# cpu_board.net
KiCad netlist of a schematic drawn in EAGLE
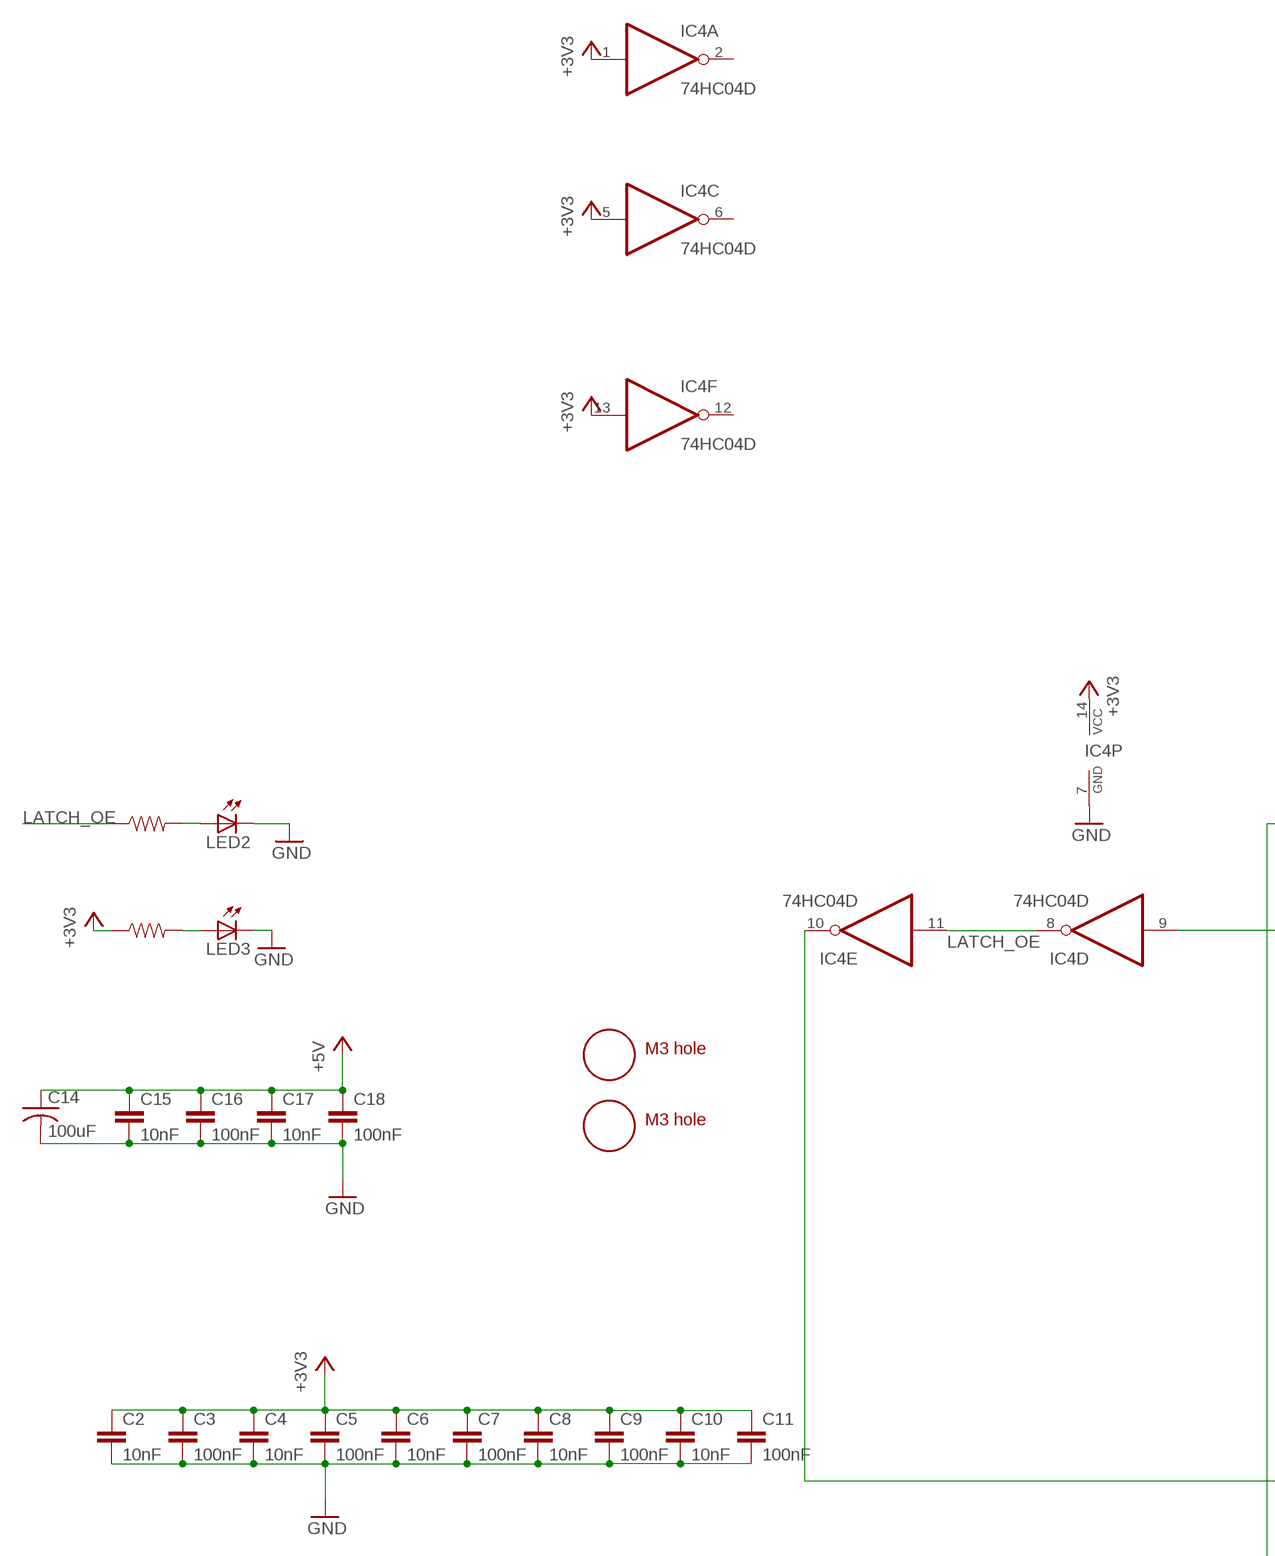
[diagram p0: schematic, sheet 1, part 1 of 2]
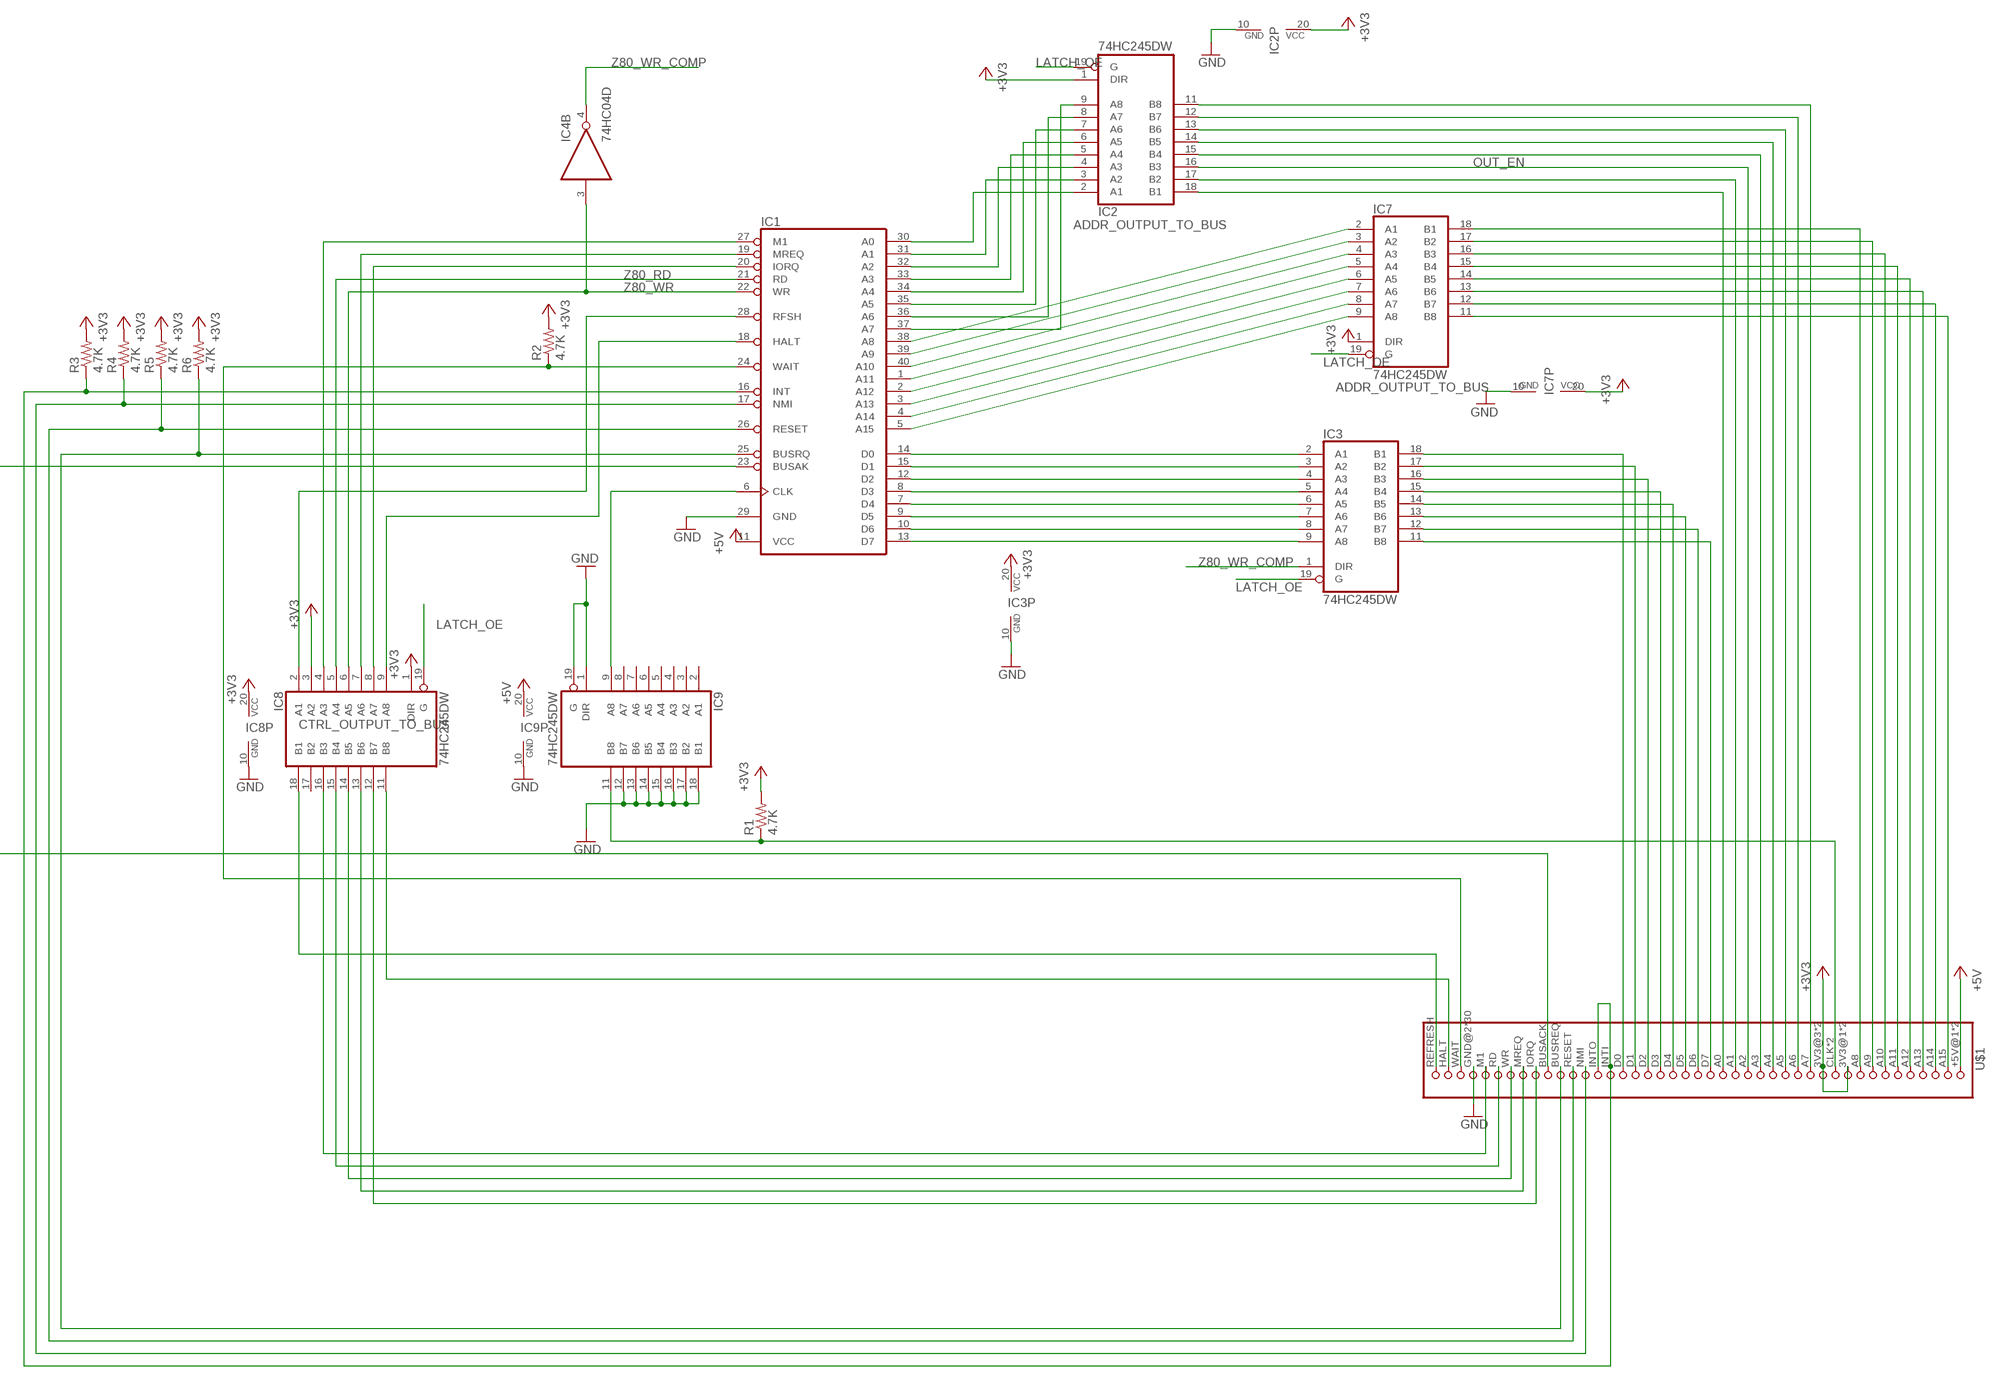
[diagram p1: schematic, sheet 1, part 2 of 2]

(export (version "E")
  (design (tool "Eeschema 10.0.6"))
  (components
    (comp (ref "C2")
      (value "10nF")
      (footprint "eagle-import:0805")
      (libsource (lib "eagle-import") (part "22UF-6.3V-20%(0805)"))
    )
    (comp (ref "C3")
      (value "100nF")
      (footprint "eagle-import:0805")
      (libsource (lib "eagle-import") (part "22UF-6.3V-20%(0805)"))
    )
    (comp (ref "C4")
      (value "10nF")
      (footprint "eagle-import:0805")
      (libsource (lib "eagle-import") (part "22UF-6.3V-20%(0805)"))
    )
    (comp (ref "C5")
      (value "100nF")
      (footprint "eagle-import:0805")
      (libsource (lib "eagle-import") (part "22UF-6.3V-20%(0805)"))
    )
    (comp (ref "C6")
      (value "10nF")
      (footprint "eagle-import:0805")
      (libsource (lib "eagle-import") (part "22UF-6.3V-20%(0805)"))
    )
    (comp (ref "C7")
      (value "100nF")
      (footprint "eagle-import:0805")
      (libsource (lib "eagle-import") (part "22UF-6.3V-20%(0805)"))
    )
    (comp (ref "C8")
      (value "10nF")
      (footprint "eagle-import:0805")
      (libsource (lib "eagle-import") (part "22UF-6.3V-20%(0805)"))
    )
    (comp (ref "C9")
      (value "100nF")
      (footprint "eagle-import:0805")
      (libsource (lib "eagle-import") (part "22UF-6.3V-20%(0805)"))
    )
    (comp (ref "C10")
      (value "10nF")
      (footprint "eagle-import:0805")
      (libsource (lib "eagle-import") (part "22UF-6.3V-20%(0805)"))
    )
    (comp (ref "C11")
      (value "100nF")
      (footprint "eagle-import:0805")
      (libsource (lib "eagle-import") (part "22UF-6.3V-20%(0805)"))
    )
    (comp (ref "C14")
      (value "100uF")
      (footprint "eagle-import:C1210")
      (libsource (lib "eagle-import") (part "C-USC1210"))
    )
    (comp (ref "C15")
      (value "10nF")
      (footprint "eagle-import:0805")
      (libsource (lib "eagle-import") (part "22UF-6.3V-20%(0805)"))
    )
    (comp (ref "C16")
      (value "100nF")
      (footprint "eagle-import:0805")
      (libsource (lib "eagle-import") (part "22UF-6.3V-20%(0805)"))
    )
    (comp (ref "C17")
      (value "10nF")
      (footprint "eagle-import:0805")
      (libsource (lib "eagle-import") (part "22UF-6.3V-20%(0805)"))
    )
    (comp (ref "C18")
      (value "100nF")
      (footprint "eagle-import:0805")
      (libsource (lib "eagle-import") (part "22UF-6.3V-20%(0805)"))
    )
    (comp (ref "IC1")
      (value "Z80CPU")
      (footprint "eagle-import:DIL40")
      (libsource (lib "eagle-import") (part "Z80CPU"))
    )
    (comp (ref "IC2")
      (value "74HC245DW")
      (footprint "eagle-import:SO20W")
      (libsource (lib "eagle-import") (part "74245DWHC"))
    )
    (comp (ref "IC3")
      (value "74HC245DW")
      (footprint "eagle-import:SO20W")
      (libsource (lib "eagle-import") (part "74245DWHC"))
    )
    (comp (ref "IC4")
      (value "74HC04D")
      (footprint "eagle-import:SO14")
      (libsource (lib "eagle-import") (part "7404DHC"))
    )
    (comp (ref "IC7")
      (value "74HC245DW")
      (footprint "eagle-import:SO20W")
      (libsource (lib "eagle-import") (part "74245DWHC"))
    )
    (comp (ref "IC8")
      (value "74HC245DW")
      (footprint "eagle-import:SO20W")
      (libsource (lib "eagle-import") (part "74245DWHC"))
    )
    (comp (ref "IC9")
      (value "74HC245DW")
      (footprint "eagle-import:SO20W")
      (libsource (lib "eagle-import") (part "74245DWHC"))
    )
    (comp (ref "LED2")
      (value "LEDCHIP-LED0805")
      (footprint "eagle-import:CHIP-LED0805")
      (libsource (lib "eagle-import") (part "LEDCHIP-LED0805"))
    )
    (comp (ref "LED3")
      (value "LEDCHIP-LED0805")
      (footprint "eagle-import:CHIP-LED0805")
      (libsource (lib "eagle-import") (part "LEDCHIP-LED0805"))
    )
    (comp (ref "R1")
      (value "4.7K")
      (footprint "eagle-import:0805")
      (libsource (lib "eagle-import") (part "SparkFun-Resistors_RESISTOR0805-RES"))
    )
    (comp (ref "R2")
      (value "4.7K")
      (footprint "eagle-import:0805")
      (libsource (lib "eagle-import") (part "SparkFun-Resistors_RESISTOR0805-RES"))
    )
    (comp (ref "R3")
      (value "4.7K")
      (footprint "eagle-import:0805")
      (libsource (lib "eagle-import") (part "SparkFun-Resistors_RESISTOR0805-RES"))
    )
    (comp (ref "R4")
      (value "4.7K")
      (footprint "eagle-import:0805")
      (libsource (lib "eagle-import") (part "SparkFun-Resistors_RESISTOR0805-RES"))
    )
    (comp (ref "R5")
      (value "4.7K")
      (footprint "eagle-import:0805")
      (libsource (lib "eagle-import") (part "SparkFun-Resistors_RESISTOR0805-RES"))
    )
    (comp (ref "R6")
      (value "4.7K")
      (footprint "eagle-import:0805")
      (libsource (lib "eagle-import") (part "SparkFun-Resistors_RESISTOR0805-RES"))
    )
    (comp (ref "R7")
      (value "2K")
      (footprint "eagle-import:0805")
      (libsource (lib "eagle-import") (part "RESISTOR0805-RES"))
    )
    (comp (ref "R8")
      (value "2K")
      (footprint "eagle-import:0805")
      (libsource (lib "eagle-import") (part "RESISTOR0805-RES"))
    )
    (comp (ref "U$1")
      (value "FAP_BUS")
      (footprint "eagle-import:2X38")
      (libsource (lib "eagle-import") (part "FAP_BUS"))
    )
    (comp (ref "U$2")
      (value "M3_MOUNTING_HOLE")
      (footprint "eagle-import:M3_MOUNTING_HOLE_PACK")
      (libsource (lib "eagle-import") (part "M3_MOUNTING_HOLE"))
    )
    (comp (ref "U$3")
      (value "M3_MOUNTING_HOLE")
      (footprint "eagle-import:M3_MOUNTING_HOLE_PACK")
      (libsource (lib "eagle-import") (part "M3_MOUNTING_HOLE"))
    )
  )
  (nets
    (net (code "1") (name "+3V3") (class "Default")
      (node (ref "C10") (pin "1") (pinfunction "1_1") (pintype "passive"))
      (node (ref "C11") (pin "1") (pinfunction "1_1") (pintype "passive"))
      (node (ref "C2") (pin "1") (pinfunction "1_1") (pintype "passive"))
      (node (ref "C3") (pin "1") (pinfunction "1_1") (pintype "passive"))
      (node (ref "C4") (pin "1") (pinfunction "1_1") (pintype "passive"))
      (node (ref "C5") (pin "1") (pinfunction "1_1") (pintype "passive"))
      (node (ref "C6") (pin "1") (pinfunction "1_1") (pintype "passive"))
      (node (ref "C7") (pin "1") (pinfunction "1_1") (pintype "passive"))
      (node (ref "C8") (pin "1") (pinfunction "1_1") (pintype "passive"))
      (node (ref "C9") (pin "1") (pinfunction "1_1") (pintype "passive"))
      (node (ref "IC2") (pin "1") (pinfunction "DIR_1") (pintype "input"))
      (node (ref "IC2") (pin "20") (pinfunction "VCC_20") (pintype "power_in"))
      (node (ref "IC3") (pin "20") (pinfunction "VCC_20") (pintype "power_in"))
      (node (ref "IC4") (pin "1") (pinfunction "I_1") (pintype "input"))
      (node (ref "IC4") (pin "13") (pinfunction "I_13") (pintype "input"))
      (node (ref "IC4") (pin "14") (pinfunction "VCC_14") (pintype "power_in"))
      (node (ref "IC4") (pin "5") (pinfunction "I_5") (pintype "input"))
      (node (ref "IC7") (pin "1") (pinfunction "DIR_1") (pintype "input"))
      (node (ref "IC7") (pin "20") (pinfunction "VCC_20") (pintype "power_in"))
      (node (ref "IC8") (pin "1") (pinfunction "DIR_1") (pintype "input"))
      (node (ref "IC8") (pin "20") (pinfunction "VCC_20") (pintype "power_in"))
      (node (ref "IC8") (pin "3") (pinfunction "A2_3") (pintype "bidirectional"))
      (node (ref "R1") (pin "2") (pinfunction "2_2") (pintype "passive"))
      (node (ref "R2") (pin "2") (pinfunction "2_2") (pintype "passive"))
      (node (ref "R3") (pin "2") (pinfunction "2_2") (pintype "passive"))
      (node (ref "R4") (pin "2") (pinfunction "2_2") (pintype "passive"))
      (node (ref "R5") (pin "2") (pinfunction "2_2") (pintype "passive"))
      (node (ref "R6") (pin "2") (pinfunction "2_2") (pintype "passive"))
      (node (ref "R8") (pin "1") (pinfunction "1_1") (pintype "passive"))
      (node (ref "U$1") (pin "3V3@1") (pinfunction "10_3V3@1") (pintype "passive"))
      (node (ref "U$1") (pin "3V3@2") (pinfunction "10_3V3@2") (pintype "passive"))
      (node (ref "U$1") (pin "3V3@3") (pinfunction "12_3V3@3") (pintype "passive"))
      (node (ref "U$1") (pin "3V3@4") (pinfunction "12_3V3@4") (pintype "passive"))
    )
    (net (code "2") (name "+5V") (class "Default")
      (node (ref "C14") (pin "1") (pinfunction "1_1") (pintype "passive"))
      (node (ref "C15") (pin "1") (pinfunction "1_1") (pintype "passive"))
      (node (ref "C16") (pin "1") (pinfunction "1_1") (pintype "passive"))
      (node (ref "C17") (pin "1") (pinfunction "1_1") (pintype "passive"))
      (node (ref "C18") (pin "1") (pinfunction "1_1") (pintype "passive"))
      (node (ref "IC1") (pin "11") (pinfunction "VCC_11") (pintype "power_in"))
      (node (ref "IC9") (pin "20") (pinfunction "VCC_20") (pintype "power_in"))
      (node (ref "U$1") (pin "+5V@1") (pinfunction "1_+5V@1") (pintype "passive"))
      (node (ref "U$1") (pin "+5V@2") (pinfunction "1_+5V@2") (pintype "passive"))
    )
    (net (code "3") (name "/LATCH_OE") (class "Default")
      (node (ref "IC2") (pin "19") (pinfunction "G_19") (pintype "input"))
      (node (ref "IC3") (pin "19") (pinfunction "G_19") (pintype "input"))
      (node (ref "IC4") (pin "11") (pinfunction "I_11") (pintype "input"))
      (node (ref "IC4") (pin "8") (pinfunction "O_8") (pintype "output"))
      (node (ref "IC7") (pin "19") (pinfunction "G_19") (pintype "input"))
      (node (ref "IC8") (pin "19") (pinfunction "G_19") (pintype "input"))
      (node (ref "R7") (pin "1") (pinfunction "1_1") (pintype "passive"))
    )
    (net (code "4") (name "/OUT_EN") (class "Default")
      (node (ref "IC2") (pin "16") (pinfunction "B3_16") (pintype "bidirectional"))
      (node (ref "U$1") (pin "A2") (pinfunction "18_A2") (pintype "passive"))
    )
    (net (code "5") (name "/Z80_RD") (class "Default")
      (node (ref "IC1") (pin "21") (pinfunction "RD_21") (pintype "output"))
      (node (ref "IC8") (pin "5") (pinfunction "A4_5") (pintype "bidirectional"))
    )
    (net (code "6") (name "/Z80_WR") (class "Default")
      (node (ref "IC1") (pin "22") (pinfunction "WR_22") (pintype "output"))
      (node (ref "IC4") (pin "3") (pinfunction "I_3") (pintype "input"))
      (node (ref "IC8") (pin "6") (pinfunction "A5_6") (pintype "bidirectional"))
    )
    (net (code "7") (name "/Z80_WR_COMP") (class "Default")
      (node (ref "IC3") (pin "1") (pinfunction "DIR_1") (pintype "input"))
      (node (ref "IC4") (pin "4") (pinfunction "O_4") (pintype "output"))
    )
    (net (code "8") (name "GND") (class "Default")
      (node (ref "C10") (pin "2") (pinfunction "2_2") (pintype "passive"))
      (node (ref "C11") (pin "2") (pinfunction "2_2") (pintype "passive"))
      (node (ref "C14") (pin "2") (pinfunction "2_2") (pintype "passive"))
      (node (ref "C15") (pin "2") (pinfunction "2_2") (pintype "passive"))
      (node (ref "C16") (pin "2") (pinfunction "2_2") (pintype "passive"))
      (node (ref "C17") (pin "2") (pinfunction "2_2") (pintype "passive"))
      (node (ref "C18") (pin "2") (pinfunction "2_2") (pintype "passive"))
      (node (ref "C2") (pin "2") (pinfunction "2_2") (pintype "passive"))
      (node (ref "C3") (pin "2") (pinfunction "2_2") (pintype "passive"))
      (node (ref "C4") (pin "2") (pinfunction "2_2") (pintype "passive"))
      (node (ref "C5") (pin "2") (pinfunction "2_2") (pintype "passive"))
      (node (ref "C6") (pin "2") (pinfunction "2_2") (pintype "passive"))
      (node (ref "C7") (pin "2") (pinfunction "2_2") (pintype "passive"))
      (node (ref "C8") (pin "2") (pinfunction "2_2") (pintype "passive"))
      (node (ref "C9") (pin "2") (pinfunction "2_2") (pintype "passive"))
      (node (ref "IC1") (pin "29") (pinfunction "GND_29") (pintype "power_in"))
      (node (ref "IC2") (pin "10") (pinfunction "GND_10") (pintype "power_in"))
      (node (ref "IC3") (pin "10") (pinfunction "GND_10") (pintype "power_in"))
      (node (ref "IC4") (pin "7") (pinfunction "GND_7") (pintype "power_in"))
      (node (ref "IC7") (pin "10") (pinfunction "GND_10") (pintype "power_in"))
      (node (ref "IC8") (pin "10") (pinfunction "GND_10") (pintype "power_in"))
      (node (ref "IC9") (pin "1") (pinfunction "DIR_1") (pintype "input"))
      (node (ref "IC9") (pin "10") (pinfunction "GND_10") (pintype "power_in"))
      (node (ref "IC9") (pin "12") (pinfunction "B7_12") (pintype "bidirectional"))
      (node (ref "IC9") (pin "13") (pinfunction "B6_13") (pintype "bidirectional"))
      (node (ref "IC9") (pin "14") (pinfunction "B5_14") (pintype "bidirectional"))
      (node (ref "IC9") (pin "15") (pinfunction "B4_15") (pintype "bidirectional"))
      (node (ref "IC9") (pin "16") (pinfunction "B3_16") (pintype "bidirectional"))
      (node (ref "IC9") (pin "17") (pinfunction "B2_17") (pintype "bidirectional"))
      (node (ref "IC9") (pin "18") (pinfunction "B1_18") (pintype "bidirectional"))
      (node (ref "IC9") (pin "19") (pinfunction "G_19") (pintype "input"))
      (node (ref "LED2") (pin "C") (pinfunction "C_C") (pintype "passive"))
      (node (ref "LED3") (pin "C") (pinfunction "C_C") (pintype "passive"))
      (node (ref "U$1") (pin "GND@13") (pinfunction "GND_GND@13") (pintype "passive"))
      (node (ref "U$1") (pin "GND@14") (pinfunction "GND_GND@14") (pintype "passive"))
      (node (ref "U$1") (pin "GND@15") (pinfunction "GND_GND@15") (pintype "passive"))
      (node (ref "U$1") (pin "GND@16") (pinfunction "GND_GND@16") (pintype "passive"))
      (node (ref "U$1") (pin "GND@17") (pinfunction "GND_GND@17") (pintype "passive"))
      (node (ref "U$1") (pin "GND@18") (pinfunction "GND_GND@18") (pintype "passive"))
      (node (ref "U$1") (pin "GND@19") (pinfunction "GND_GND@19") (pintype "passive"))
      (node (ref "U$1") (pin "GND@2") (pinfunction "GND_GND@2") (pintype "passive"))
      (node (ref "U$1") (pin "GND@20") (pinfunction "GND_GND@20") (pintype "passive"))
      (node (ref "U$1") (pin "GND@21") (pinfunction "GND_GND@21") (pintype "passive"))
      (node (ref "U$1") (pin "GND@22") (pinfunction "GND_GND@22") (pintype "passive"))
      (node (ref "U$1") (pin "GND@23") (pinfunction "GND_GND@23") (pintype "passive"))
      (node (ref "U$1") (pin "GND@24") (pinfunction "GND_GND@24") (pintype "passive"))
      (node (ref "U$1") (pin "GND@25") (pinfunction "GND_GND@25") (pintype "passive"))
      (node (ref "U$1") (pin "GND@26") (pinfunction "GND_GND@26") (pintype "passive"))
      (node (ref "U$1") (pin "GND@27") (pinfunction "GND_GND@27") (pintype "passive"))
      (node (ref "U$1") (pin "GND@28") (pinfunction "GND_GND@28") (pintype "passive"))
      (node (ref "U$1") (pin "GND@3") (pinfunction "GND_GND@3") (pintype "passive"))
      (node (ref "U$1") (pin "GND@30") (pinfunction "GND_GND@30") (pintype "passive"))
      (node (ref "U$1") (pin "GND@34") (pinfunction "GND_GND@34") (pintype "passive"))
      (node (ref "U$1") (pin "GND@35") (pinfunction "GND_GND@35") (pintype "passive"))
      (node (ref "U$1") (pin "GND@36") (pinfunction "GND_GND@36") (pintype "passive"))
      (node (ref "U$1") (pin "GND@37") (pinfunction "GND_GND@37") (pintype "passive"))
      (node (ref "U$1") (pin "GND@38") (pinfunction "GND_GND@38") (pintype "passive"))
      (node (ref "U$1") (pin "GND@4") (pinfunction "GND_GND@4") (pintype "passive"))
      (node (ref "U$1") (pin "GND@5") (pinfunction "GND_GND@5") (pintype "passive"))
      (node (ref "U$1") (pin "GND@6") (pinfunction "GND_GND@6") (pintype "passive"))
      (node (ref "U$1") (pin "GND@7") (pinfunction "GND_GND@7") (pintype "passive"))
      (node (ref "U$1") (pin "GND@8") (pinfunction "GND_GND@8") (pintype "passive"))
      (node (ref "U$1") (pin "GND@9") (pinfunction "GND_GND@9") (pintype "passive"))
    )
    (net (code "9") (name "Net-(IC1-A0)") (class "Default")
      (node (ref "IC1") (pin "30") (pinfunction "A0_30") (pintype "output"))
      (node (ref "IC2") (pin "2") (pinfunction "A1_2") (pintype "bidirectional"))
    )
    (net (code "10") (name "Net-(IC1-A1)") (class "Default")
      (node (ref "IC1") (pin "31") (pinfunction "A1_31") (pintype "output"))
      (node (ref "IC2") (pin "3") (pinfunction "A2_3") (pintype "bidirectional"))
    )
    (net (code "11") (name "Net-(IC1-A2)") (class "Default")
      (node (ref "IC1") (pin "32") (pinfunction "A2_32") (pintype "output"))
      (node (ref "IC2") (pin "4") (pinfunction "A3_4") (pintype "bidirectional"))
    )
    (net (code "12") (name "Net-(IC1-A3)") (class "Default")
      (node (ref "IC1") (pin "33") (pinfunction "A3_33") (pintype "output"))
      (node (ref "IC2") (pin "5") (pinfunction "A4_5") (pintype "bidirectional"))
    )
    (net (code "13") (name "Net-(IC1-A4)") (class "Default")
      (node (ref "IC1") (pin "34") (pinfunction "A4_34") (pintype "output"))
      (node (ref "IC2") (pin "6") (pinfunction "A5_6") (pintype "bidirectional"))
    )
    (net (code "14") (name "Net-(IC1-A5)") (class "Default")
      (node (ref "IC1") (pin "35") (pinfunction "A5_35") (pintype "output"))
      (node (ref "IC2") (pin "7") (pinfunction "A6_7") (pintype "bidirectional"))
    )
    (net (code "15") (name "Net-(IC1-A6)") (class "Default")
      (node (ref "IC1") (pin "36") (pinfunction "A6_36") (pintype "output"))
      (node (ref "IC2") (pin "8") (pinfunction "A7_8") (pintype "bidirectional"))
    )
    (net (code "16") (name "Net-(IC1-A7)") (class "Default")
      (node (ref "IC1") (pin "37") (pinfunction "A7_37") (pintype "output"))
      (node (ref "IC2") (pin "9") (pinfunction "A8_9") (pintype "bidirectional"))
    )
    (net (code "17") (name "Net-(IC1-A8)") (class "Default")
      (node (ref "IC1") (pin "38") (pinfunction "A8_38") (pintype "output"))
      (node (ref "IC7") (pin "2") (pinfunction "A1_2") (pintype "bidirectional"))
    )
    (net (code "18") (name "Net-(IC1-A9)") (class "Default")
      (node (ref "IC1") (pin "39") (pinfunction "A9_39") (pintype "output"))
      (node (ref "IC7") (pin "3") (pinfunction "A2_3") (pintype "bidirectional"))
    )
    (net (code "19") (name "Net-(IC1-A10)") (class "Default")
      (node (ref "IC1") (pin "40") (pinfunction "A10_40") (pintype "output"))
      (node (ref "IC7") (pin "4") (pinfunction "A3_4") (pintype "bidirectional"))
    )
    (net (code "20") (name "Net-(IC1-A11)") (class "Default")
      (node (ref "IC1") (pin "1") (pinfunction "A11_1") (pintype "output"))
      (node (ref "IC7") (pin "5") (pinfunction "A4_5") (pintype "bidirectional"))
    )
    (net (code "21") (name "Net-(IC1-A12)") (class "Default")
      (node (ref "IC1") (pin "2") (pinfunction "A12_2") (pintype "output"))
      (node (ref "IC7") (pin "6") (pinfunction "A5_6") (pintype "bidirectional"))
    )
    (net (code "22") (name "Net-(IC1-A13)") (class "Default")
      (node (ref "IC1") (pin "3") (pinfunction "A13_3") (pintype "output"))
      (node (ref "IC7") (pin "7") (pinfunction "A6_7") (pintype "bidirectional"))
    )
    (net (code "23") (name "Net-(IC1-A14)") (class "Default")
      (node (ref "IC1") (pin "4") (pinfunction "A14_4") (pintype "output"))
      (node (ref "IC7") (pin "8") (pinfunction "A7_8") (pintype "bidirectional"))
    )
    (net (code "24") (name "Net-(IC1-A15)") (class "Default")
      (node (ref "IC1") (pin "5") (pinfunction "A15_5") (pintype "output"))
      (node (ref "IC7") (pin "9") (pinfunction "A8_9") (pintype "bidirectional"))
    )
    (net (code "25") (name "Net-(IC1-BUSAK)") (class "Default")
      (node (ref "IC1") (pin "23") (pinfunction "BUSAK_23") (pintype "output"))
      (node (ref "IC4") (pin "9") (pinfunction "I_9") (pintype "input"))
    )
    (net (code "26") (name "Net-(IC1-BUSRQ)") (class "Default")
      (node (ref "IC1") (pin "25") (pinfunction "BUSRQ_25") (pintype "input"))
      (node (ref "R6") (pin "1") (pinfunction "1_1") (pintype "passive"))
      (node (ref "U$1") (pin "BUSREQ") (pinfunction "32_BUSREQ") (pintype "passive"))
    )
    (net (code "27") (name "Net-(IC1-CLK)") (class "Default")
      (node (ref "IC1") (pin "6") (pinfunction "CLK_6") (pintype "input"))
      (node (ref "IC9") (pin "9") (pinfunction "A8_9") (pintype "bidirectional"))
    )
    (net (code "28") (name "Net-(IC1-D0)") (class "Default")
      (node (ref "IC1") (pin "14") (pinfunction "D0_14") (pintype "bidirectional"))
      (node (ref "IC3") (pin "2") (pinfunction "A1_2") (pintype "bidirectional"))
    )
    (net (code "29") (name "Net-(IC1-D1)") (class "Default")
      (node (ref "IC1") (pin "15") (pinfunction "D1_15") (pintype "bidirectional"))
      (node (ref "IC3") (pin "3") (pinfunction "A2_3") (pintype "bidirectional"))
    )
    (net (code "30") (name "Net-(IC1-D2)") (class "Default")
      (node (ref "IC1") (pin "12") (pinfunction "D2_12") (pintype "bidirectional"))
      (node (ref "IC3") (pin "4") (pinfunction "A3_4") (pintype "bidirectional"))
    )
    (net (code "31") (name "Net-(IC1-D3)") (class "Default")
      (node (ref "IC1") (pin "8") (pinfunction "D3_8") (pintype "bidirectional"))
      (node (ref "IC3") (pin "5") (pinfunction "A4_5") (pintype "bidirectional"))
    )
    (net (code "32") (name "Net-(IC1-D4)") (class "Default")
      (node (ref "IC1") (pin "7") (pinfunction "D4_7") (pintype "bidirectional"))
      (node (ref "IC3") (pin "6") (pinfunction "A5_6") (pintype "bidirectional"))
    )
    (net (code "33") (name "Net-(IC1-D5)") (class "Default")
      (node (ref "IC1") (pin "9") (pinfunction "D5_9") (pintype "bidirectional"))
      (node (ref "IC3") (pin "7") (pinfunction "A6_7") (pintype "bidirectional"))
    )
    (net (code "34") (name "Net-(IC1-D6)") (class "Default")
      (node (ref "IC1") (pin "10") (pinfunction "D6_10") (pintype "bidirectional"))
      (node (ref "IC3") (pin "8") (pinfunction "A7_8") (pintype "bidirectional"))
    )
    (net (code "35") (name "Net-(IC1-D7)") (class "Default")
      (node (ref "IC1") (pin "13") (pinfunction "D7_13") (pintype "bidirectional"))
      (node (ref "IC3") (pin "9") (pinfunction "A8_9") (pintype "bidirectional"))
    )
    (net (code "36") (name "Net-(IC1-HALT)") (class "Default")
      (node (ref "IC1") (pin "18") (pinfunction "HALT_18") (pintype "output"))
      (node (ref "IC8") (pin "9") (pinfunction "A8_9") (pintype "bidirectional"))
    )
    (net (code "37") (name "Net-(IC1-INT)") (class "Default")
      (node (ref "IC1") (pin "16") (pinfunction "INT_16") (pintype "input"))
      (node (ref "R3") (pin "1") (pinfunction "1_1") (pintype "passive"))
      (node (ref "U$1") (pin "INTI") (pinfunction "29_INTI") (pintype "passive"))
      (node (ref "U$1") (pin "INTO") (pinfunction "39_INTO") (pintype "passive"))
    )
    (net (code "38") (name "Net-(IC1-IORQ)") (class "Default")
      (node (ref "IC1") (pin "20") (pinfunction "IORQ_20") (pintype "output"))
      (node (ref "IC8") (pin "8") (pinfunction "A7_8") (pintype "bidirectional"))
    )
    (net (code "39") (name "Net-(IC1-M1)") (class "Default")
      (node (ref "IC1") (pin "27") (pinfunction "M1_27") (pintype "output"))
      (node (ref "IC8") (pin "4") (pinfunction "A3_4") (pintype "bidirectional"))
    )
    (net (code "40") (name "Net-(IC1-MREQ)") (class "Default")
      (node (ref "IC1") (pin "19") (pinfunction "MREQ_19") (pintype "output"))
      (node (ref "IC8") (pin "7") (pinfunction "A6_7") (pintype "bidirectional"))
    )
    (net (code "41") (name "Net-(IC1-NMI)") (class "Default")
      (node (ref "IC1") (pin "17") (pinfunction "NMI_17") (pintype "input"))
      (node (ref "R4") (pin "1") (pinfunction "1_1") (pintype "passive"))
      (node (ref "U$1") (pin "NMI") (pinfunction "30_NMI") (pintype "passive"))
    )
    (net (code "42") (name "Net-(IC1-RESET)") (class "Default")
      (node (ref "IC1") (pin "26") (pinfunction "RESET_26") (pintype "input"))
      (node (ref "R5") (pin "1") (pinfunction "1_1") (pintype "passive"))
      (node (ref "U$1") (pin "RESET") (pinfunction "31_RESET") (pintype "passive"))
    )
    (net (code "43") (name "Net-(IC1-RFSH)") (class "Default")
      (node (ref "IC1") (pin "28") (pinfunction "RFSH_28") (pintype "output"))
      (node (ref "IC8") (pin "2") (pinfunction "A1_2") (pintype "bidirectional"))
    )
    (net (code "44") (name "Net-(IC1-WAIT)") (class "Default")
      (node (ref "IC1") (pin "24") (pinfunction "WAIT_24") (pintype "input"))
      (node (ref "R2") (pin "1") (pinfunction "1_1") (pintype "passive"))
      (node (ref "U$1") (pin "WAIT") (pinfunction "40_WAIT") (pintype "passive"))
    )
    (net (code "45") (name "Net-(IC2A-B1)") (class "Default")
      (node (ref "IC2") (pin "18") (pinfunction "B1_18") (pintype "bidirectional"))
      (node (ref "U$1") (pin "A0") (pinfunction "20_A0") (pintype "passive"))
    )
    (net (code "46") (name "Net-(IC2A-B2)") (class "Default")
      (node (ref "IC2") (pin "17") (pinfunction "B2_17") (pintype "bidirectional"))
      (node (ref "U$1") (pin "A1") (pinfunction "19_A1") (pintype "passive"))
    )
    (net (code "47") (name "Net-(IC2A-B4)") (class "Default")
      (node (ref "IC2") (pin "15") (pinfunction "B4_15") (pintype "bidirectional"))
      (node (ref "U$1") (pin "A3") (pinfunction "17_A3") (pintype "passive"))
    )
    (net (code "48") (name "Net-(IC2A-B5)") (class "Default")
      (node (ref "IC2") (pin "14") (pinfunction "B5_14") (pintype "bidirectional"))
      (node (ref "U$1") (pin "A4") (pinfunction "16_A4") (pintype "passive"))
    )
    (net (code "49") (name "Net-(IC2A-B6)") (class "Default")
      (node (ref "IC2") (pin "13") (pinfunction "B6_13") (pintype "bidirectional"))
      (node (ref "U$1") (pin "A5") (pinfunction "15_A5") (pintype "passive"))
    )
    (net (code "50") (name "Net-(IC2A-B7)") (class "Default")
      (node (ref "IC2") (pin "12") (pinfunction "B7_12") (pintype "bidirectional"))
      (node (ref "U$1") (pin "A6") (pinfunction "14_A6") (pintype "passive"))
    )
    (net (code "51") (name "Net-(IC2A-B8)") (class "Default")
      (node (ref "IC2") (pin "11") (pinfunction "B8_11") (pintype "bidirectional"))
      (node (ref "U$1") (pin "A7") (pinfunction "13_A7") (pintype "passive"))
    )
    (net (code "52") (name "Net-(IC3A-B1)") (class "Default")
      (node (ref "IC3") (pin "18") (pinfunction "B1_18") (pintype "bidirectional"))
      (node (ref "U$1") (pin "D0") (pinfunction "28_D0") (pintype "passive"))
    )
    (net (code "53") (name "Net-(IC3A-B2)") (class "Default")
      (node (ref "IC3") (pin "17") (pinfunction "B2_17") (pintype "bidirectional"))
      (node (ref "U$1") (pin "D1") (pinfunction "27_D1") (pintype "passive"))
    )
    (net (code "54") (name "Net-(IC3A-B3)") (class "Default")
      (node (ref "IC3") (pin "16") (pinfunction "B3_16") (pintype "bidirectional"))
      (node (ref "U$1") (pin "D2") (pinfunction "26_D2") (pintype "passive"))
    )
    (net (code "55") (name "Net-(IC3A-B4)") (class "Default")
      (node (ref "IC3") (pin "15") (pinfunction "B4_15") (pintype "bidirectional"))
      (node (ref "U$1") (pin "D3") (pinfunction "25_D3") (pintype "passive"))
    )
    (net (code "56") (name "Net-(IC3A-B5)") (class "Default")
      (node (ref "IC3") (pin "14") (pinfunction "B5_14") (pintype "bidirectional"))
      (node (ref "U$1") (pin "D4") (pinfunction "24_D4") (pintype "passive"))
    )
    (net (code "57") (name "Net-(IC3A-B6)") (class "Default")
      (node (ref "IC3") (pin "13") (pinfunction "B6_13") (pintype "bidirectional"))
      (node (ref "U$1") (pin "D5") (pinfunction "23_D5") (pintype "passive"))
    )
    (net (code "58") (name "Net-(IC3A-B7)") (class "Default")
      (node (ref "IC3") (pin "12") (pinfunction "B7_12") (pintype "bidirectional"))
      (node (ref "U$1") (pin "D6") (pinfunction "22_D6") (pintype "passive"))
    )
    (net (code "59") (name "Net-(IC3A-B8)") (class "Default")
      (node (ref "IC3") (pin "11") (pinfunction "B8_11") (pintype "bidirectional"))
      (node (ref "U$1") (pin "D7") (pinfunction "21_D7") (pintype "passive"))
    )
    (net (code "60") (name "Net-(IC4E-O)") (class "Default")
      (node (ref "IC4") (pin "10") (pinfunction "O_10") (pintype "output"))
      (node (ref "U$1") (pin "BUSACK") (pinfunction "33_BUSACK") (pintype "passive"))
    )
    (net (code "61") (name "Net-(IC7A-B1)") (class "Default")
      (node (ref "IC7") (pin "18") (pinfunction "B1_18") (pintype "bidirectional"))
      (node (ref "U$1") (pin "A8") (pinfunction "9_A8") (pintype "passive"))
    )
    (net (code "62") (name "Net-(IC7A-B2)") (class "Default")
      (node (ref "IC7") (pin "17") (pinfunction "B2_17") (pintype "bidirectional"))
      (node (ref "U$1") (pin "A9") (pinfunction "8_A9") (pintype "passive"))
    )
    (net (code "63") (name "Net-(IC7A-B3)") (class "Default")
      (node (ref "IC7") (pin "16") (pinfunction "B3_16") (pintype "bidirectional"))
      (node (ref "U$1") (pin "A10") (pinfunction "7_A10") (pintype "passive"))
    )
    (net (code "64") (name "Net-(IC7A-B4)") (class "Default")
      (node (ref "IC7") (pin "15") (pinfunction "B4_15") (pintype "bidirectional"))
      (node (ref "U$1") (pin "A11") (pinfunction "6_A11") (pintype "passive"))
    )
    (net (code "65") (name "Net-(IC7A-B5)") (class "Default")
      (node (ref "IC7") (pin "14") (pinfunction "B5_14") (pintype "bidirectional"))
      (node (ref "U$1") (pin "A12") (pinfunction "5_A12") (pintype "passive"))
    )
    (net (code "66") (name "Net-(IC7A-B6)") (class "Default")
      (node (ref "IC7") (pin "13") (pinfunction "B6_13") (pintype "bidirectional"))
      (node (ref "U$1") (pin "A13") (pinfunction "4_A13") (pintype "passive"))
    )
    (net (code "67") (name "Net-(IC7A-B7)") (class "Default")
      (node (ref "IC7") (pin "12") (pinfunction "B7_12") (pintype "bidirectional"))
      (node (ref "U$1") (pin "A14") (pinfunction "3_A14") (pintype "passive"))
    )
    (net (code "68") (name "Net-(IC7A-B8)") (class "Default")
      (node (ref "IC7") (pin "11") (pinfunction "B8_11") (pintype "bidirectional"))
      (node (ref "U$1") (pin "A15") (pinfunction "2_A15") (pintype "passive"))
    )
    (net (code "69") (name "Net-(IC8A-B1)") (class "Default")
      (node (ref "IC8") (pin "18") (pinfunction "B1_18") (pintype "bidirectional"))
      (node (ref "U$1") (pin "REFRESH") (pinfunction "42_REFRESH") (pintype "passive"))
    )
    (net (code "70") (name "Net-(IC8A-B3)") (class "Default")
      (node (ref "IC8") (pin "16") (pinfunction "B3_16") (pintype "bidirectional"))
      (node (ref "U$1") (pin "M1") (pinfunction "38_M1") (pintype "passive"))
    )
    (net (code "71") (name "Net-(IC8A-B4)") (class "Default")
      (node (ref "IC8") (pin "15") (pinfunction "B4_15") (pintype "bidirectional"))
      (node (ref "U$1") (pin "RD") (pinfunction "37_RD") (pintype "passive"))
    )
    (net (code "72") (name "Net-(IC8A-B5)") (class "Default")
      (node (ref "IC8") (pin "14") (pinfunction "B5_14") (pintype "bidirectional"))
      (node (ref "U$1") (pin "WR") (pinfunction "36_WR") (pintype "passive"))
    )
    (net (code "73") (name "Net-(IC8A-B6)") (class "Default")
      (node (ref "IC8") (pin "13") (pinfunction "B6_13") (pintype "bidirectional"))
      (node (ref "U$1") (pin "MREQ") (pinfunction "35_MREQ") (pintype "passive"))
    )
    (net (code "74") (name "Net-(IC8A-B7)") (class "Default")
      (node (ref "IC8") (pin "12") (pinfunction "B7_12") (pintype "bidirectional"))
      (node (ref "U$1") (pin "IORQ") (pinfunction "34_IORQ") (pintype "passive"))
    )
    (net (code "75") (name "Net-(IC8A-B8)") (class "Default")
      (node (ref "IC8") (pin "11") (pinfunction "B8_11") (pintype "bidirectional"))
      (node (ref "U$1") (pin "HALT") (pinfunction "41_HALT") (pintype "passive"))
    )
    (net (code "76") (name "Net-(IC9A-B8)") (class "Default")
      (node (ref "IC9") (pin "11") (pinfunction "B8_11") (pintype "bidirectional"))
      (node (ref "R1") (pin "1") (pinfunction "1_1") (pintype "passive"))
      (node (ref "U$1") (pin "CLK") (pinfunction "11_CLK") (pintype "passive"))
      (node (ref "U$1") (pin "CLK@2") (pinfunction "11_CLK@2") (pintype "passive"))
    )
    (net (code "77") (name "Net-(LED2-PadA)") (class "Default")
      (node (ref "LED2") (pin "A") (pinfunction "A_A") (pintype "passive"))
      (node (ref "R7") (pin "2") (pinfunction "2_2") (pintype "passive"))
    )
    (net (code "78") (name "Net-(LED3-PadA)") (class "Default")
      (node (ref "LED3") (pin "A") (pinfunction "A_A") (pintype "passive"))
      (node (ref "R8") (pin "2") (pinfunction "2_2") (pintype "passive"))
    )
    (net (code "79") (name "unconnected-(IC4A-O-Pad2)") (class "Default")
      (node (ref "IC4") (pin "2") (pinfunction "O_2") (pintype "output"))
    )
    (net (code "80") (name "unconnected-(IC4C-O-Pad6)") (class "Default")
      (node (ref "IC4") (pin "6") (pinfunction "O_6") (pintype "output"))
    )
    (net (code "81") (name "unconnected-(IC4F-O-Pad12)") (class "Default")
      (node (ref "IC4") (pin "12") (pinfunction "O_12") (pintype "output"))
    )
    (net (code "82") (name "unconnected-(IC8A-B2-Pad17)") (class "Default")
      (node (ref "IC8") (pin "17") (pinfunction "B2_17") (pintype "bidirectional"))
    )
    (net (code "83") (name "unconnected-(IC9A-A1-Pad2)") (class "Default")
      (node (ref "IC9") (pin "2") (pinfunction "A1_2") (pintype "bidirectional"))
    )
    (net (code "84") (name "unconnected-(IC9A-A2-Pad3)") (class "Default")
      (node (ref "IC9") (pin "3") (pinfunction "A2_3") (pintype "bidirectional"))
    )
    (net (code "85") (name "unconnected-(IC9A-A3-Pad4)") (class "Default")
      (node (ref "IC9") (pin "4") (pinfunction "A3_4") (pintype "bidirectional"))
    )
    (net (code "86") (name "unconnected-(IC9A-A4-Pad5)") (class "Default")
      (node (ref "IC9") (pin "5") (pinfunction "A4_5") (pintype "bidirectional"))
    )
    (net (code "87") (name "unconnected-(IC9A-A5-Pad6)") (class "Default")
      (node (ref "IC9") (pin "6") (pinfunction "A5_6") (pintype "bidirectional"))
    )
    (net (code "88") (name "unconnected-(IC9A-A6-Pad7)") (class "Default")
      (node (ref "IC9") (pin "7") (pinfunction "A6_7") (pintype "bidirectional"))
    )
    (net (code "89") (name "unconnected-(IC9A-A7-Pad8)") (class "Default")
      (node (ref "IC9") (pin "8") (pinfunction "A7_8") (pintype "bidirectional"))
    )
  )
)
